# SCH_chimenea_2022-03-22.net
KiCad netlist of a schematic drawn in EasyEDA
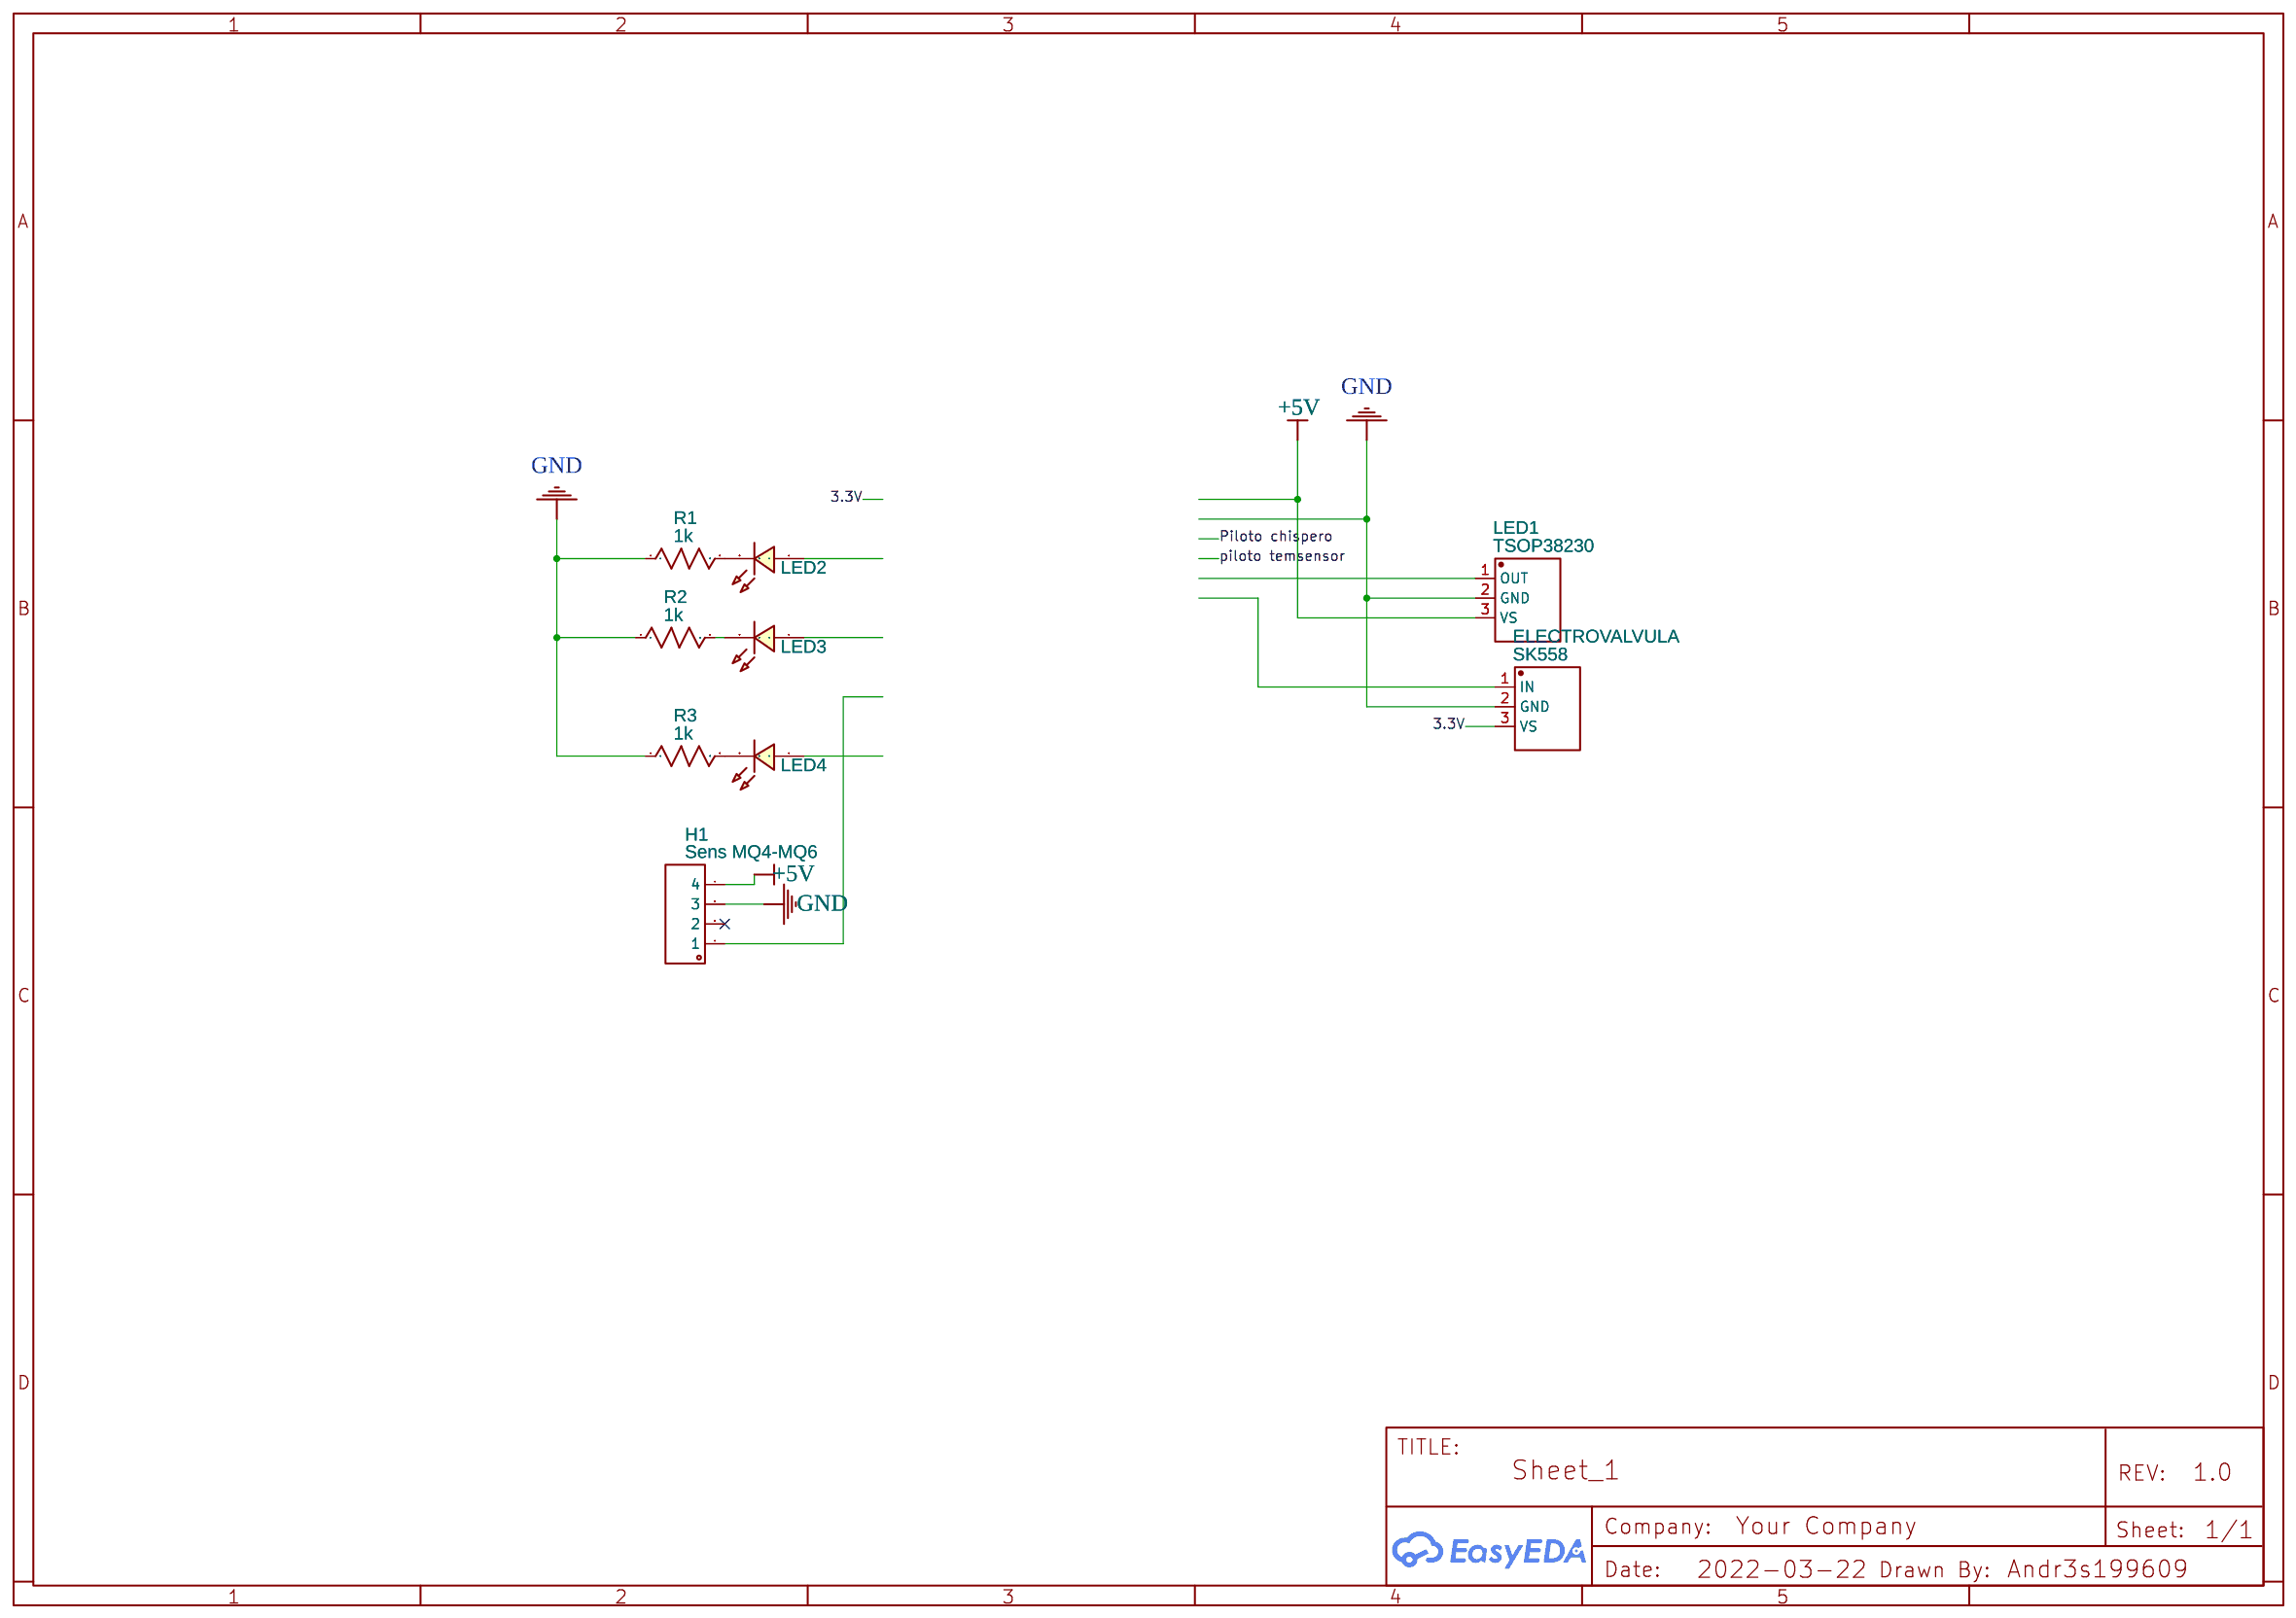
[diagram p0: schematic sheet]

(export (version "E")
  (design (tool "Eeschema 10.0.6"))
  (components
    (comp (ref "ELECTROVALVULA")
      (value "SK558")
      (fields (field (name "BOM_Manufacturer Part") "TSOP38238") (field (name "BOM_Supplier Part") "C141632"))
      (libsource (lib "") (part "TSOP38238"))
    )
    (comp (ref "H1")
      (value "Sens MQ4-MQ6")
      (fields
        (field (name "BOM_Manufacturer Part") "210S-1*4P L=11.6MMGold-plated black")
        (field (name "BOM_Supplier Part") "C124378")
      )
      (libsource (lib "") (part "Unknown_345_-350"))
    )
    (comp (ref "LED1")
      (value "TSOP38230")
      (fields (field (name "BOM_Manufacturer Part") "TSOP38238") (field (name "BOM_Supplier Part") "C141632"))
      (libsource (lib "") (part "TSOP38238_1"))
    )
    (comp (ref "LED2")
      (value "LED-0603_R")
      (fields
        (field (name "BOM_Manufacturer Part") "19-217/R6C-AL1M2VY/3T")
        (field (name "BOM_Supplier Part") "C72044")
      )
      (libsource (lib "") (part "LED-0603_R"))
    )
    (comp (ref "LED3")
      (value "LED-0603_R")
      (fields
        (field (name "BOM_Manufacturer Part") "19-217/R6C-AL1M2VY/3T")
        (field (name "BOM_Supplier Part") "C72044")
      )
      (libsource (lib "") (part "LED-0603_R"))
    )
    (comp (ref "LED4")
      (value "LED-0603_R")
      (fields
        (field (name "BOM_Manufacturer Part") "19-217/R6C-AL1M2VY/3T")
        (field (name "BOM_Supplier Part") "C72044")
      )
      (libsource (lib "") (part "LED-0603_R"))
    )
    (comp (ref "R1") (value "1k") (libsource (lib "") (part "R_0603_US")))
    (comp (ref "R2") (value "1k") (libsource (lib "") (part "R_0603_US")))
    (comp (ref "R3") (value "1k") (libsource (lib "") (part "R_0603_US")))
  )
  (nets
    (net (code "1") (name "+5V") (class "Default")
      (node (ref "H1") (pin "4") (pinfunction "4_4") (pintype "unspecified"))
      (node (ref "LED1") (pin "3") (pinfunction "VS_3") (pintype "unspecified"))
    )
    (net (code "2") (name "/3.3V") (class "Default")
      (node (ref "ELECTROVALVULA") (pin "3") (pinfunction "VS_3") (pintype "unspecified"))
    )
    (net (code "5") (name "GND") (class "Default")
      (node (ref "ELECTROVALVULA") (pin "2") (pinfunction "GND_2") (pintype "unspecified"))
      (node (ref "H1") (pin "3") (pinfunction "3_3") (pintype "unspecified"))
      (node (ref "LED1") (pin "2") (pinfunction "GND_2") (pintype "unspecified"))
      (node (ref "R1") (pin "1") (pinfunction "1_1") (pintype "unspecified"))
      (node (ref "R2") (pin "1") (pinfunction "1_1") (pintype "unspecified"))
      (node (ref "R3") (pin "1") (pinfunction "1_1") (pintype "unspecified"))
    )
    (net (code "6") (name "Net-(LED2-Pad2)") (class "Default")
      (node (ref "LED2") (pin "2") (pinfunction "2_2") (pintype "unspecified"))
      (node (ref "R1") (pin "2") (pinfunction "2_2") (pintype "unspecified"))
    )
    (net (code "7") (name "Net-(LED3-Pad2)") (class "Default")
      (node (ref "LED3") (pin "2") (pinfunction "2_2") (pintype "unspecified"))
      (node (ref "R2") (pin "2") (pinfunction "2_2") (pintype "unspecified"))
    )
    (net (code "8") (name "Net-(LED4-Pad2)") (class "Default")
      (node (ref "LED4") (pin "2") (pinfunction "2_2") (pintype "unspecified"))
      (node (ref "R3") (pin "2") (pinfunction "2_2") (pintype "unspecified"))
    )
    (net (code "9") (name "unconnected-(ELECTROVALVULA-IN-Pad1)") (class "Default")
      (node (ref "ELECTROVALVULA") (pin "1") (pinfunction "IN_1") (pintype "unspecified"))
    )
    (net (code "10") (name "unconnected-(H1-Pad1)") (class "Default")
      (node (ref "H1") (pin "1") (pinfunction "1_1") (pintype "unspecified"))
    )
    (net (code "11") (name "unconnected-(H1-Pad2)") (class "Default")
      (node (ref "H1") (pin "2") (pinfunction "2_2") (pintype "unspecified+no_connect"))
    )
    (net (code "12") (name "unconnected-(LED1-OUT-Pad1)") (class "Default")
      (node (ref "LED1") (pin "1") (pinfunction "OUT_1") (pintype "unspecified"))
    )
    (net (code "13") (name "unconnected-(LED2-Pad1)") (class "Default")
      (node (ref "LED2") (pin "1") (pinfunction "1_1") (pintype "unspecified"))
    )
    (net (code "14") (name "unconnected-(LED3-Pad1)") (class "Default")
      (node (ref "LED3") (pin "1") (pinfunction "1_1") (pintype "unspecified"))
    )
    (net (code "15") (name "unconnected-(LED4-Pad1)") (class "Default")
      (node (ref "LED4") (pin "1") (pinfunction "1_1") (pintype "unspecified"))
    )
  )
)
